# light.net
KiCad netlist of a schematic drawn in EAGLE
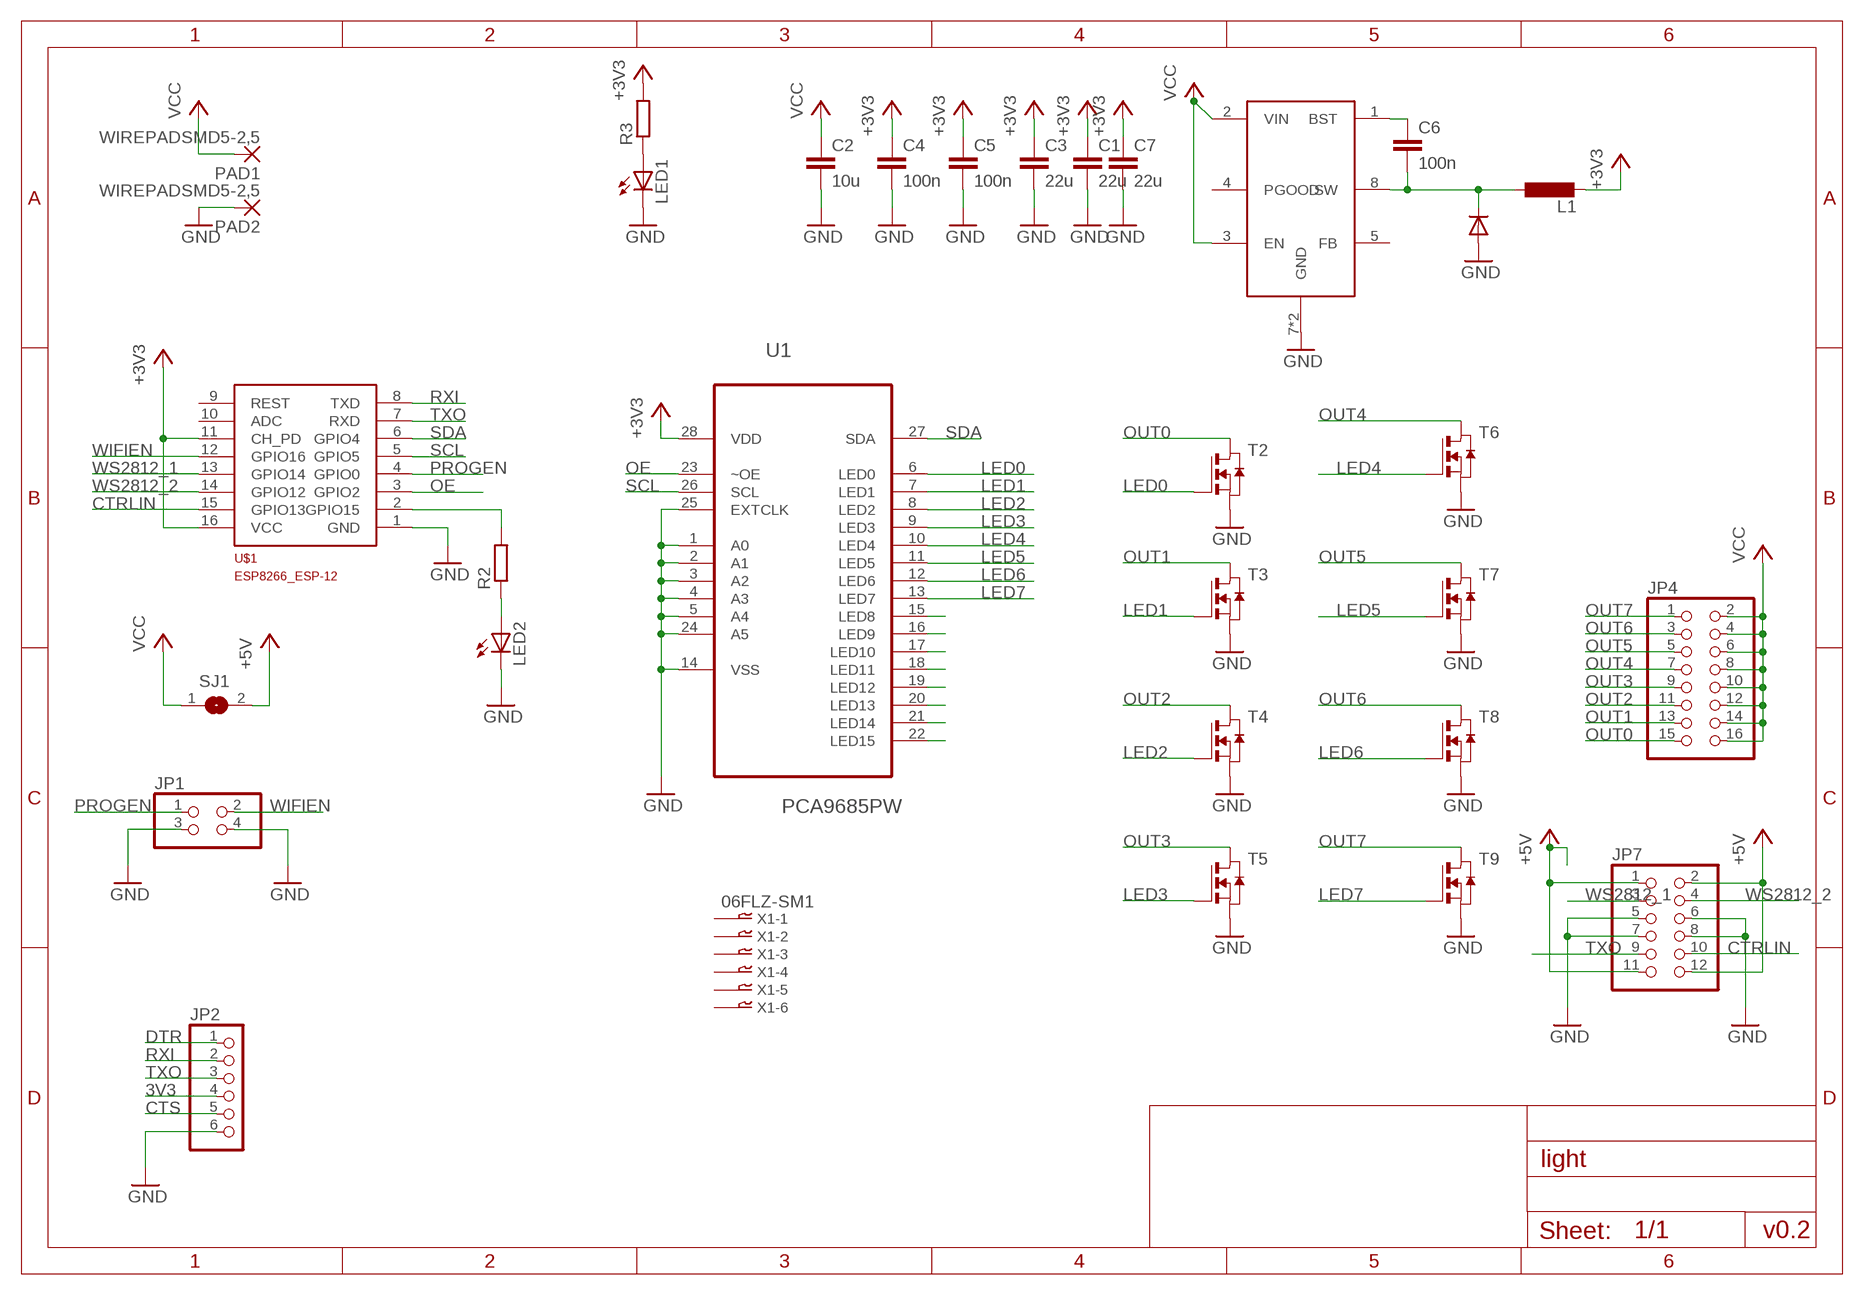
[diagram p0: schematic, sheet 1]

(export (version "E")
  (design (tool "Eeschema 10.0.6"))
  (components
    (comp (ref "C1")
      (value "22u")
      (footprint "eagle-import:C0805K")
      (libsource (lib "eagle-import") (part "C-EUC0805K"))
    )
    (comp (ref "C2")
      (value "10u")
      (footprint "eagle-import:C0805K")
      (libsource (lib "eagle-import") (part "C-EUC0805K"))
    )
    (comp (ref "C3")
      (value "22u")
      (footprint "eagle-import:C0805K")
      (libsource (lib "eagle-import") (part "C-EUC0805K"))
    )
    (comp (ref "C4")
      (value "100n")
      (footprint "eagle-import:C0603K")
      (libsource (lib "eagle-import") (part "C-EUC0603K"))
    )
    (comp (ref "C5")
      (value "100n")
      (footprint "eagle-import:C0603K")
      (libsource (lib "eagle-import") (part "C-EUC0603K"))
    )
    (comp (ref "C6")
      (value "100n")
      (footprint "eagle-import:C0603K")
      (libsource (lib "eagle-import") (part "C-EUC0603K"))
    )
    (comp (ref "C7")
      (value "22u")
      (footprint "eagle-import:C0805K")
      (libsource (lib "eagle-import") (part "C-EUC0805K"))
    )
    (comp (ref "JP1")
      (value "PINHD-2X2")
      (footprint "eagle-import:2X02")
      (libsource (lib "eagle-import") (part "PINHD-2X2"))
    )
    (comp (ref "JP2")
      (value "PINHD-1X6")
      (footprint "eagle-import:1X06")
      (libsource (lib "eagle-import") (part "PINHD-1X6"))
    )
    (comp (ref "JP4")
      (value "PINHD-2X8")
      (footprint "eagle-import:2X08")
      (libsource (lib "eagle-import") (part "PINHD-2X8"))
    )
    (comp (ref "JP7")
      (value "PINHD-2X6")
      (footprint "eagle-import:2X06")
      (libsource (lib "eagle-import") (part "PINHD-2X6"))
    )
    (comp (ref "L1")
      (value "L-EUL5650M")
      (footprint "eagle-import:L5650M")
      (libsource (lib "eagle-import") (part "L-EUL5650M"))
    )
    (comp (ref "LED1")
      (value "LEDSML0603")
      (footprint "eagle-import:SML0603")
      (libsource (lib "eagle-import") (part "LEDSML0603"))
    )
    (comp (ref "LED2")
      (value "LEDSML0603")
      (footprint "eagle-import:SML0603")
      (libsource (lib "eagle-import") (part "LEDSML0603"))
    )
    (comp (ref "PAD1")
      (value "WIREPADSMD5-2,5")
      (footprint "eagle-import:5-2,5")
      (libsource (lib "eagle-import") (part "WIREPADSMD5-2,5"))
    )
    (comp (ref "PAD2")
      (value "WIREPADSMD5-2,5")
      (footprint "eagle-import:5-2,5")
      (libsource (lib "eagle-import") (part "WIREPADSMD5-2,5"))
    )
    (comp (ref "R2")
      (value "R-EU_R0603")
      (footprint "eagle-import:R0603")
      (libsource (lib "eagle-import") (part "R-EU_R0603"))
    )
    (comp (ref "R3")
      (value "R-EU_R0603")
      (footprint "eagle-import:R0603")
      (libsource (lib "eagle-import") (part "R-EU_R0603"))
    )
    (comp (ref "SJ1") (value "SJ") (footprint "eagle-import:SJ") (libsource (lib "eagle-import") (part "SJ")))
    (comp (ref "T2")
      (value "NMOSSOT23")
      (footprint "eagle-import:SOT-23")
      (libsource (lib "eagle-import") (part "NMOSSOT23"))
    )
    (comp (ref "T3")
      (value "NMOSSOT23")
      (footprint "eagle-import:SOT-23")
      (libsource (lib "eagle-import") (part "NMOSSOT23"))
    )
    (comp (ref "T4")
      (value "NMOSSOT23")
      (footprint "eagle-import:SOT-23")
      (libsource (lib "eagle-import") (part "NMOSSOT23"))
    )
    (comp (ref "T5")
      (value "NMOSSOT23")
      (footprint "eagle-import:SOT-23")
      (libsource (lib "eagle-import") (part "NMOSSOT23"))
    )
    (comp (ref "T6")
      (value "NMOSSOT23")
      (footprint "eagle-import:SOT-23")
      (libsource (lib "eagle-import") (part "NMOSSOT23"))
    )
    (comp (ref "T7")
      (value "NMOSSOT23")
      (footprint "eagle-import:SOT-23")
      (libsource (lib "eagle-import") (part "NMOSSOT23"))
    )
    (comp (ref "T8")
      (value "NMOSSOT23")
      (footprint "eagle-import:SOT-23")
      (libsource (lib "eagle-import") (part "NMOSSOT23"))
    )
    (comp (ref "T9")
      (value "NMOSSOT23")
      (footprint "eagle-import:SOT-23")
      (libsource (lib "eagle-import") (part "NMOSSOT23"))
    )
    (comp (ref "U$1")
      (value "ESP8266_ESP-12")
      (footprint "eagle-import:ESP8266-ESP12")
      (libsource (lib "eagle-import") (part "ESP8266_ESP-12"))
    )
    (comp (ref "U$2")
      (value "ADP2302")
      (footprint "eagle-import:SOIC8G-1.27-5X4MM")
      (libsource (lib "eagle-import") (part "ADP2302"))
    )
    (comp (ref "U$3")
      (value "SSB43L")
      (footprint "eagle-import:DO-214AA")
      (libsource (lib "eagle-import") (part "SSB43L"))
    )
    (comp (ref "U1")
      (value "PCA9685PW")
      (footprint "eagle-import:SOP65P640X110-28N")
      (libsource (lib "eagle-import") (part "PCA9685PW"))
    )
    (comp (ref "X1")
      (value "06FLZ-SM1")
      (footprint "eagle-import:6FLZ-SM")
      (libsource (lib "eagle-import") (part "06FLZ-SM1"))
    )
  )
  (nets
    (net (code "1") (name "+3V3") (class "Default")
      (node (ref "C1") (pin "1") (pinfunction "1_1") (pintype "passive"))
      (node (ref "C3") (pin "1") (pinfunction "1_1") (pintype "passive"))
      (node (ref "C4") (pin "1") (pinfunction "1_1") (pintype "passive"))
      (node (ref "C5") (pin "1") (pinfunction "1_1") (pintype "passive"))
      (node (ref "C7") (pin "1") (pinfunction "1_1") (pintype "passive"))
      (node (ref "L1") (pin "2") (pinfunction "2_2") (pintype "passive"))
      (node (ref "R3") (pin "2") (pinfunction "2_2") (pintype "passive"))
      (node (ref "U$1") (pin "11") (pinfunction "CH_PD_11") (pintype "bidirectional"))
      (node (ref "U$1") (pin "16") (pinfunction "VCC_16") (pintype "bidirectional"))
      (node (ref "U1") (pin "28") (pinfunction "VDD_28") (pintype "power_in"))
    )
    (net (code "2") (name "+5V") (class "Default")
      (node (ref "JP7") (pin "1") (pinfunction "1_1") (pintype "passive"))
      (node (ref "JP7") (pin "11") (pinfunction "11_11") (pintype "passive"))
      (node (ref "JP7") (pin "12") (pinfunction "12_12") (pintype "passive"))
      (node (ref "JP7") (pin "2") (pinfunction "2_2") (pintype "passive"))
      (node (ref "SJ1") (pin "2") (pinfunction "2_2") (pintype "passive"))
    )
    (net (code "3") (name "/3V3") (class "Default")
      (node (ref "JP2") (pin "4") (pinfunction "4_4") (pintype "passive"))
    )
    (net (code "4") (name "/CTRLIN") (class "Default")
      (node (ref "JP7") (pin "10") (pinfunction "10_10") (pintype "passive"))
      (node (ref "U$1") (pin "15") (pinfunction "GPIO13_15") (pintype "bidirectional"))
    )
    (net (code "5") (name "/CTS") (class "Default")
      (node (ref "JP2") (pin "5") (pinfunction "5_5") (pintype "passive"))
    )
    (net (code "6") (name "/DTR") (class "Default")
      (node (ref "JP2") (pin "1") (pinfunction "1_1") (pintype "passive"))
    )
    (net (code "7") (name "/LED0") (class "Default")
      (node (ref "T2") (pin "3") (pinfunction "G_3") (pintype "passive"))
      (node (ref "U1") (pin "6") (pinfunction "LED0_6") (pintype "output"))
    )
    (net (code "8") (name "/LED1") (class "Default")
      (node (ref "T3") (pin "3") (pinfunction "G_3") (pintype "passive"))
      (node (ref "U1") (pin "7") (pinfunction "LED1_7") (pintype "output"))
    )
    (net (code "9") (name "/LED2") (class "Default")
      (node (ref "T4") (pin "3") (pinfunction "G_3") (pintype "passive"))
      (node (ref "U1") (pin "8") (pinfunction "LED2_8") (pintype "output"))
    )
    (net (code "10") (name "/LED3") (class "Default")
      (node (ref "T5") (pin "3") (pinfunction "G_3") (pintype "passive"))
      (node (ref "U1") (pin "9") (pinfunction "LED3_9") (pintype "output"))
    )
    (net (code "11") (name "/LED4") (class "Default")
      (node (ref "T6") (pin "3") (pinfunction "G_3") (pintype "passive"))
      (node (ref "U1") (pin "10") (pinfunction "LED4_10") (pintype "output"))
    )
    (net (code "12") (name "/LED5") (class "Default")
      (node (ref "T7") (pin "3") (pinfunction "G_3") (pintype "passive"))
      (node (ref "U1") (pin "11") (pinfunction "LED5_11") (pintype "output"))
    )
    (net (code "13") (name "/LED6") (class "Default")
      (node (ref "T8") (pin "3") (pinfunction "G_3") (pintype "passive"))
      (node (ref "U1") (pin "12") (pinfunction "LED6_12") (pintype "output"))
    )
    (net (code "14") (name "/LED7") (class "Default")
      (node (ref "T9") (pin "3") (pinfunction "G_3") (pintype "passive"))
      (node (ref "U1") (pin "13") (pinfunction "LED7_13") (pintype "output"))
    )
    (net (code "15") (name "/OE") (class "Default")
      (node (ref "U$1") (pin "3") (pinfunction "GPIO2_3") (pintype "bidirectional"))
      (node (ref "U1") (pin "23") (pinfunction "~{OE}_23") (pintype "input"))
    )
    (net (code "16") (name "/OUT0") (class "Default")
      (node (ref "JP4") (pin "15") (pinfunction "15_15") (pintype "passive"))
      (node (ref "T2") (pin "1") (pinfunction "D_1") (pintype "passive"))
    )
    (net (code "17") (name "/OUT1") (class "Default")
      (node (ref "JP4") (pin "13") (pinfunction "13_13") (pintype "passive"))
      (node (ref "T3") (pin "1") (pinfunction "D_1") (pintype "passive"))
    )
    (net (code "18") (name "/OUT2") (class "Default")
      (node (ref "JP4") (pin "11") (pinfunction "11_11") (pintype "passive"))
      (node (ref "T4") (pin "1") (pinfunction "D_1") (pintype "passive"))
    )
    (net (code "19") (name "/OUT3") (class "Default")
      (node (ref "JP4") (pin "9") (pinfunction "9_9") (pintype "passive"))
      (node (ref "T5") (pin "1") (pinfunction "D_1") (pintype "passive"))
    )
    (net (code "20") (name "/OUT4") (class "Default")
      (node (ref "JP4") (pin "7") (pinfunction "7_7") (pintype "passive"))
      (node (ref "T6") (pin "1") (pinfunction "D_1") (pintype "passive"))
    )
    (net (code "21") (name "/OUT5") (class "Default")
      (node (ref "JP4") (pin "5") (pinfunction "5_5") (pintype "passive"))
      (node (ref "T7") (pin "1") (pinfunction "D_1") (pintype "passive"))
    )
    (net (code "22") (name "/OUT6") (class "Default")
      (node (ref "JP4") (pin "3") (pinfunction "3_3") (pintype "passive"))
      (node (ref "T8") (pin "1") (pinfunction "D_1") (pintype "passive"))
    )
    (net (code "23") (name "/OUT7") (class "Default")
      (node (ref "JP4") (pin "1") (pinfunction "1_1") (pintype "passive"))
      (node (ref "T9") (pin "1") (pinfunction "D_1") (pintype "passive"))
    )
    (net (code "24") (name "/PROGEN") (class "Default")
      (node (ref "JP1") (pin "1") (pinfunction "1_1") (pintype "passive"))
      (node (ref "U$1") (pin "4") (pinfunction "GPIO0_4") (pintype "bidirectional"))
    )
    (net (code "25") (name "/RXI") (class "Default")
      (node (ref "JP2") (pin "2") (pinfunction "2_2") (pintype "passive"))
      (node (ref "U$1") (pin "8") (pinfunction "TXD_8") (pintype "bidirectional"))
    )
    (net (code "26") (name "/SCL") (class "Default")
      (node (ref "U$1") (pin "5") (pinfunction "GPIO5_5") (pintype "bidirectional"))
      (node (ref "U1") (pin "26") (pinfunction "SCL_26") (pintype "input"))
    )
    (net (code "27") (name "/SDA") (class "Default")
      (node (ref "U$1") (pin "6") (pinfunction "GPIO4_6") (pintype "bidirectional"))
      (node (ref "U1") (pin "27") (pinfunction "SDA_27") (pintype "bidirectional"))
    )
    (net (code "28") (name "/TXO") (class "Default")
      (node (ref "JP2") (pin "3") (pinfunction "3_3") (pintype "passive"))
      (node (ref "JP7") (pin "9") (pinfunction "9_9") (pintype "passive"))
      (node (ref "U$1") (pin "7") (pinfunction "RXD_7") (pintype "bidirectional"))
    )
    (net (code "29") (name "/WIFIEN") (class "Default")
      (node (ref "JP1") (pin "2") (pinfunction "2_2") (pintype "passive"))
      (node (ref "U$1") (pin "12") (pinfunction "GPIO16_12") (pintype "bidirectional"))
    )
    (net (code "30") (name "/WS2812_1") (class "Default")
      (node (ref "JP7") (pin "3") (pinfunction "3_3") (pintype "passive"))
      (node (ref "U$1") (pin "13") (pinfunction "GPIO14_13") (pintype "bidirectional"))
    )
    (net (code "31") (name "/WS2812_2") (class "Default")
      (node (ref "JP7") (pin "4") (pinfunction "4_4") (pintype "passive"))
      (node (ref "U$1") (pin "14") (pinfunction "GPIO12_14") (pintype "bidirectional"))
    )
    (net (code "32") (name "GND") (class "Default")
      (node (ref "C1") (pin "2") (pinfunction "2_2") (pintype "passive"))
      (node (ref "C2") (pin "2") (pinfunction "2_2") (pintype "passive"))
      (node (ref "C3") (pin "2") (pinfunction "2_2") (pintype "passive"))
      (node (ref "C4") (pin "2") (pinfunction "2_2") (pintype "passive"))
      (node (ref "C5") (pin "2") (pinfunction "2_2") (pintype "passive"))
      (node (ref "C7") (pin "2") (pinfunction "2_2") (pintype "passive"))
      (node (ref "JP1") (pin "3") (pinfunction "3_3") (pintype "passive"))
      (node (ref "JP1") (pin "4") (pinfunction "4_4") (pintype "passive"))
      (node (ref "JP2") (pin "6") (pinfunction "6_6") (pintype "passive"))
      (node (ref "JP7") (pin "5") (pinfunction "5_5") (pintype "passive"))
      (node (ref "JP7") (pin "6") (pinfunction "6_6") (pintype "passive"))
      (node (ref "JP7") (pin "7") (pinfunction "7_7") (pintype "passive"))
      (node (ref "JP7") (pin "8") (pinfunction "8_8") (pintype "passive"))
      (node (ref "LED1") (pin "C") (pinfunction "C_C") (pintype "passive"))
      (node (ref "LED2") (pin "C") (pinfunction "C_C") (pintype "passive"))
      (node (ref "PAD2") (pin "1") (pinfunction "P_1") (pintype "passive"))
      (node (ref "T2") (pin "2") (pinfunction "S_2") (pintype "passive"))
      (node (ref "T3") (pin "2") (pinfunction "S_2") (pintype "passive"))
      (node (ref "T4") (pin "2") (pinfunction "S_2") (pintype "passive"))
      (node (ref "T5") (pin "2") (pinfunction "S_2") (pintype "passive"))
      (node (ref "T6") (pin "2") (pinfunction "S_2") (pintype "passive"))
      (node (ref "T7") (pin "2") (pinfunction "S_2") (pintype "passive"))
      (node (ref "T8") (pin "2") (pinfunction "S_2") (pintype "passive"))
      (node (ref "T9") (pin "2") (pinfunction "S_2") (pintype "passive"))
      (node (ref "U$1") (pin "1") (pinfunction "GND_1") (pintype "bidirectional"))
      (node (ref "U$2") (pin "7") (pinfunction "GND_7") (pintype "bidirectional"))
      (node (ref "U$2") (pin "PAD") (pinfunction "GND_PAD") (pintype "bidirectional"))
      (node (ref "U$3") (pin "+") (pinfunction "A_+") (pintype "bidirectional"))
      (node (ref "U1") (pin "1") (pinfunction "A0_1") (pintype "input"))
      (node (ref "U1") (pin "14") (pinfunction "VSS_14") (pintype "passive"))
      (node (ref "U1") (pin "2") (pinfunction "A1_2") (pintype "input"))
      (node (ref "U1") (pin "24") (pinfunction "A5_24") (pintype "input"))
      (node (ref "U1") (pin "25") (pinfunction "EXTCLK_25") (pintype "input"))
      (node (ref "U1") (pin "3") (pinfunction "A2_3") (pintype "input"))
      (node (ref "U1") (pin "4") (pinfunction "A3_4") (pintype "input"))
      (node (ref "U1") (pin "5") (pinfunction "A4_5") (pintype "input"))
    )
    (net (code "33") (name "Net-(LED1-PadA)") (class "Default")
      (node (ref "LED1") (pin "A") (pinfunction "A_A") (pintype "passive"))
      (node (ref "R3") (pin "1") (pinfunction "1_1") (pintype "passive"))
    )
    (net (code "34") (name "Net-(LED2-PadA)") (class "Default")
      (node (ref "LED2") (pin "A") (pinfunction "A_A") (pintype "passive"))
      (node (ref "R2") (pin "1") (pinfunction "1_1") (pintype "passive"))
    )
    (net (code "35") (name "Net-(U$1-GPIO15)") (class "Default")
      (node (ref "R2") (pin "2") (pinfunction "2_2") (pintype "passive"))
      (node (ref "U$1") (pin "2") (pinfunction "GPIO15_2") (pintype "bidirectional"))
    )
    (net (code "36") (name "Net-(U$2-BST)") (class "Default")
      (node (ref "C6") (pin "1") (pinfunction "1_1") (pintype "passive"))
      (node (ref "U$2") (pin "1") (pinfunction "BST_1") (pintype "bidirectional"))
    )
    (net (code "37") (name "Net-(U$2-SW)") (class "Default")
      (node (ref "C6") (pin "2") (pinfunction "2_2") (pintype "passive"))
      (node (ref "L1") (pin "1") (pinfunction "1_1") (pintype "passive"))
      (node (ref "U$2") (pin "8") (pinfunction "SW_8") (pintype "bidirectional"))
      (node (ref "U$3") (pin "-") (pinfunction "C_-") (pintype "bidirectional"))
    )
    (net (code "38") (name "VCC") (class "Default")
      (node (ref "C2") (pin "1") (pinfunction "1_1") (pintype "passive"))
      (node (ref "JP4") (pin "10") (pinfunction "10_10") (pintype "passive"))
      (node (ref "JP4") (pin "12") (pinfunction "12_12") (pintype "passive"))
      (node (ref "JP4") (pin "14") (pinfunction "14_14") (pintype "passive"))
      (node (ref "JP4") (pin "16") (pinfunction "16_16") (pintype "passive"))
      (node (ref "JP4") (pin "2") (pinfunction "2_2") (pintype "passive"))
      (node (ref "JP4") (pin "4") (pinfunction "4_4") (pintype "passive"))
      (node (ref "JP4") (pin "6") (pinfunction "6_6") (pintype "passive"))
      (node (ref "JP4") (pin "8") (pinfunction "8_8") (pintype "passive"))
      (node (ref "PAD1") (pin "1") (pinfunction "P_1") (pintype "passive"))
      (node (ref "SJ1") (pin "1") (pinfunction "1_1") (pintype "passive"))
      (node (ref "U$2") (pin "2") (pinfunction "VIN_2") (pintype "bidirectional"))
      (node (ref "U$2") (pin "3") (pinfunction "EN_3") (pintype "bidirectional"))
    )
    (net (code "39") (name "unconnected-(U$1-ADC-Pad10)") (class "Default")
      (node (ref "U$1") (pin "10") (pinfunction "ADC_10") (pintype "bidirectional"))
    )
    (net (code "40") (name "unconnected-(U$1-REST-Pad9)") (class "Default")
      (node (ref "U$1") (pin "9") (pinfunction "REST_9") (pintype "bidirectional"))
    )
    (net (code "41") (name "unconnected-(U$2-FB-Pad5)") (class "Default")
      (node (ref "U$2") (pin "5") (pinfunction "FB_5") (pintype "bidirectional"))
    )
    (net (code "42") (name "unconnected-(U$2-PGOOD-Pad4)") (class "Default")
      (node (ref "U$2") (pin "4") (pinfunction "PGOOD_4") (pintype "bidirectional"))
    )
    (net (code "43") (name "unconnected-(U1-LED8-Pad15)") (class "Default")
      (node (ref "U1") (pin "15") (pinfunction "LED8_15") (pintype "output"))
    )
    (net (code "44") (name "unconnected-(U1-LED9-Pad16)") (class "Default")
      (node (ref "U1") (pin "16") (pinfunction "LED9_16") (pintype "output"))
    )
    (net (code "45") (name "unconnected-(U1-LED10-Pad17)") (class "Default")
      (node (ref "U1") (pin "17") (pinfunction "LED10_17") (pintype "output"))
    )
    (net (code "46") (name "unconnected-(U1-LED11-Pad18)") (class "Default")
      (node (ref "U1") (pin "18") (pinfunction "LED11_18") (pintype "output"))
    )
    (net (code "47") (name "unconnected-(U1-LED12-Pad19)") (class "Default")
      (node (ref "U1") (pin "19") (pinfunction "LED12_19") (pintype "output"))
    )
    (net (code "48") (name "unconnected-(U1-LED13-Pad20)") (class "Default")
      (node (ref "U1") (pin "20") (pinfunction "LED13_20") (pintype "output"))
    )
    (net (code "49") (name "unconnected-(U1-LED14-Pad21)") (class "Default")
      (node (ref "U1") (pin "21") (pinfunction "LED14_21") (pintype "output"))
    )
    (net (code "50") (name "unconnected-(U1-LED15-Pad22)") (class "Default")
      (node (ref "U1") (pin "22") (pinfunction "LED15_22") (pintype "output"))
    )
    (net (code "51") (name "unconnected-(X1-Pad1)") (class "Default")
      (node (ref "X1") (pin "1") (pinfunction "1_1") (pintype "passive"))
    )
    (net (code "52") (name "unconnected-(X1B-1-Pad2)") (class "Default")
      (node (ref "X1") (pin "2") (pinfunction "1_2") (pintype "passive"))
    )
    (net (code "53") (name "unconnected-(X1C-1-Pad3)") (class "Default")
      (node (ref "X1") (pin "3") (pinfunction "1_3") (pintype "passive"))
    )
    (net (code "54") (name "unconnected-(X1D-1-Pad4)") (class "Default")
      (node (ref "X1") (pin "4") (pinfunction "1_4") (pintype "passive"))
    )
    (net (code "55") (name "unconnected-(X1E-1-Pad5)") (class "Default")
      (node (ref "X1") (pin "5") (pinfunction "1_5") (pintype "passive"))
    )
    (net (code "56") (name "unconnected-(X1F-1-Pad6)") (class "Default")
      (node (ref "X1") (pin "6") (pinfunction "1_6") (pintype "passive"))
    )
  )
)
